# RAWX_Logger_Switches.net
KiCad netlist of a schematic drawn in EAGLE
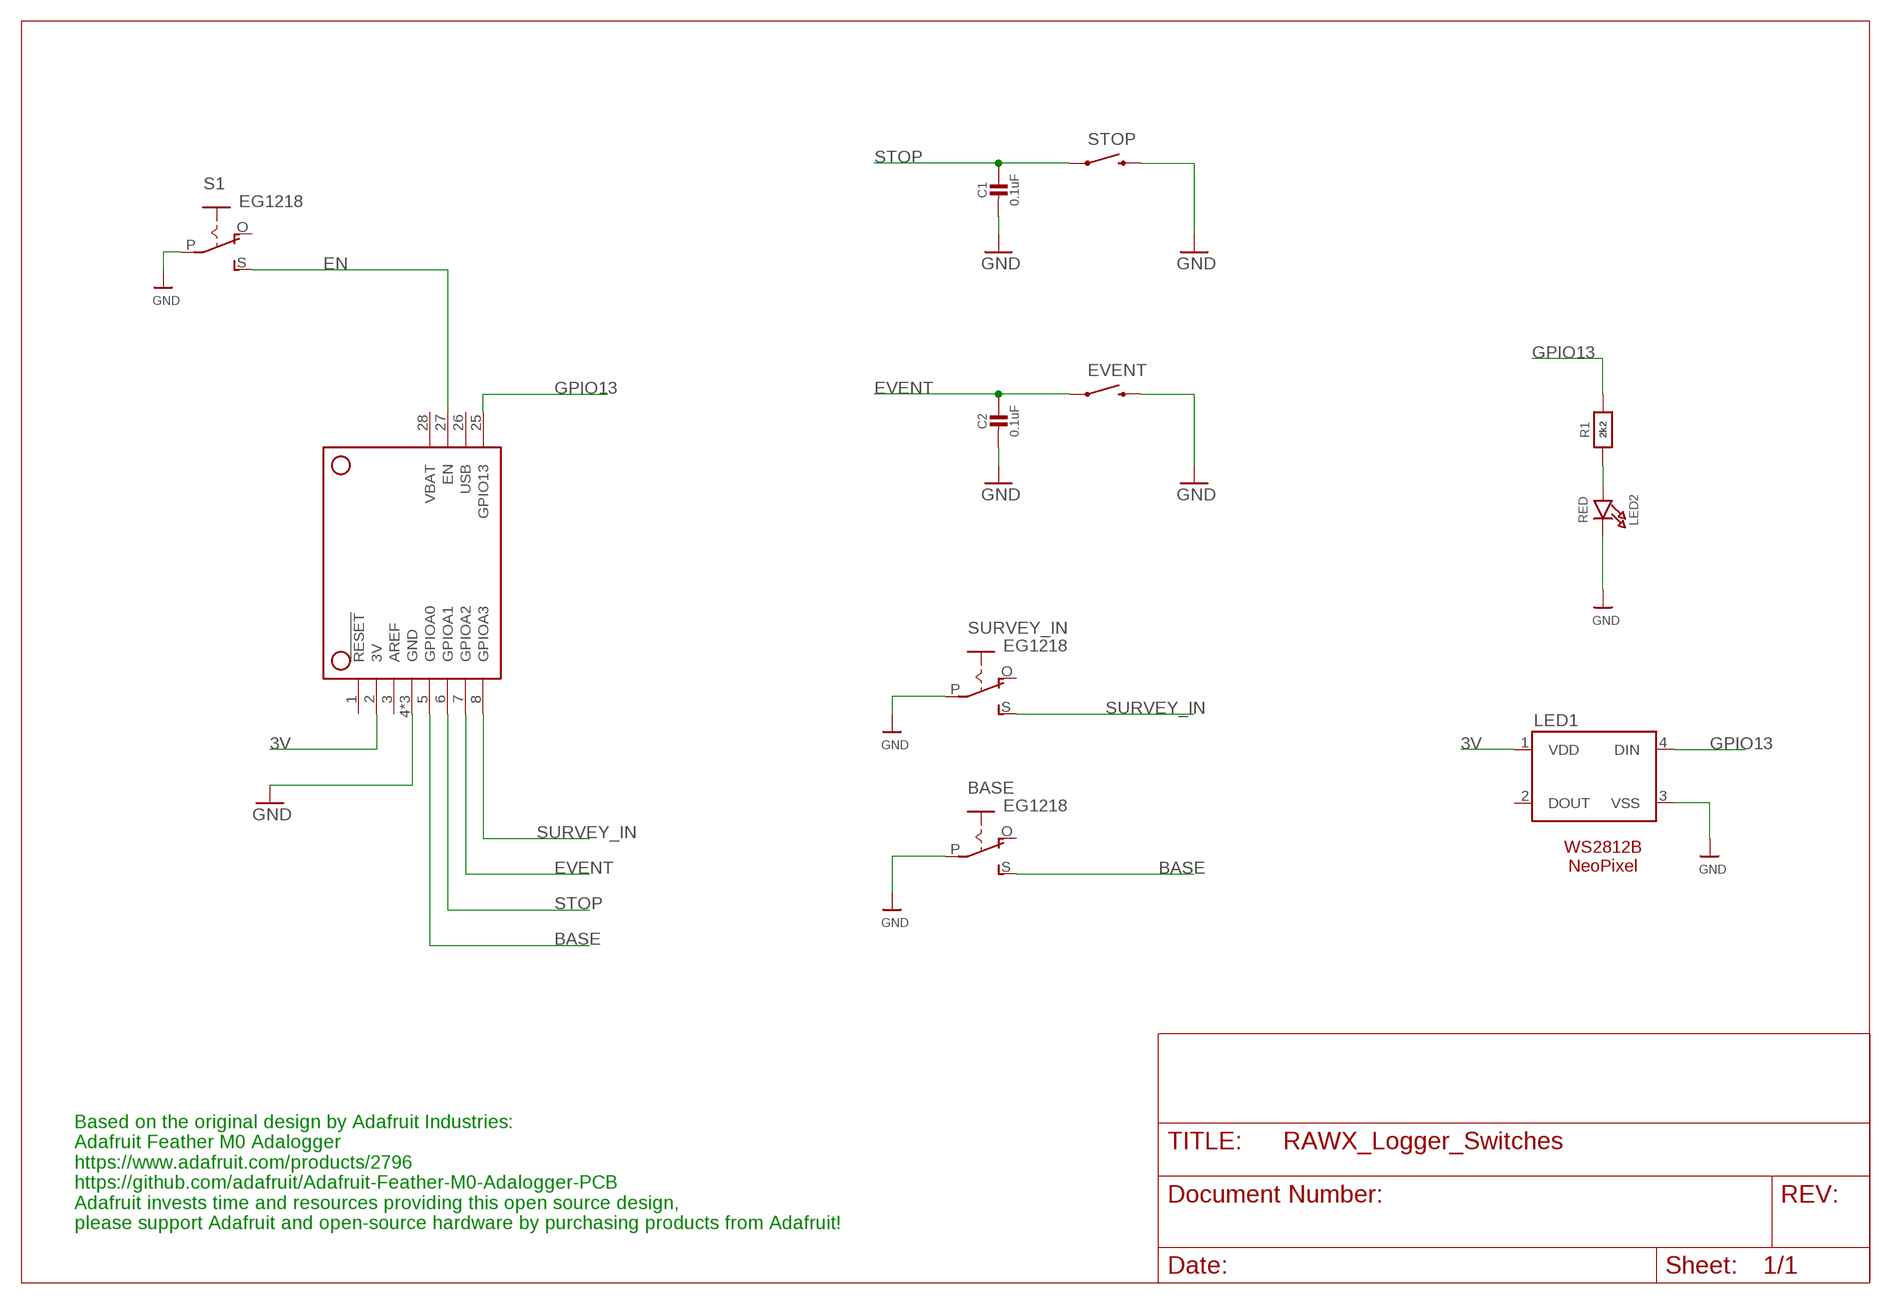
[diagram p0: schematic, sheet 1]

(export (version "E")
  (design (tool "Eeschema 10.0.6"))
  (components
    (comp (ref "BASE")
      (value "EG1218")
      (footprint "eagle-import:EG1218")
      (libsource (lib "eagle-import") (part "EG1218S"))
    )
    (comp (ref "C1")
      (value "0.1uF")
      (footprint "eagle-import:0603-NO")
      (libsource (lib "eagle-import") (part "CAP_CERAMIC0603_NO"))
    )
    (comp (ref "C2")
      (value "0.1uF")
      (footprint "eagle-import:0603-NO")
      (libsource (lib "eagle-import") (part "CAP_CERAMIC0603_NO"))
    )
    (comp (ref "EVENT")
      (value "SWITCH-MOMENTARY-2PTH")
      (footprint "eagle-import:TACTILE-PTH")
      (libsource (lib "eagle-import") (part "SWITCH-MOMENTARY-2PTH"))
    )
    (comp (ref "LED1")
      (value "WS2812B")
      (footprint "eagle-import:WS2812B")
      (libsource (lib "eagle-import") (part "WS2812B"))
    )
    (comp (ref "LED2")
      (value "RED")
      (footprint "eagle-import:CHIPLED_0805_NOOUTLINE")
      (libsource (lib "eagle-import") (part "LED0805_NOOUTLINE"))
    )
    (comp (ref "MS1")
      (value "MICROBUILDER_FEATHERWING_EN_SWITCH")
      (footprint "eagle-import:MICROBUILDER_FEATHERWING_EN_SWITCH")
      (libsource (lib "eagle-import") (part "MICROBUILDER_FEATHERWING_EN_SWITCH"))
    )
    (comp (ref "R1")
      (value "2k2")
      (footprint "eagle-import:0805-NO")
      (libsource (lib "eagle-import") (part "RESISTOR0805_NOOUTLINE"))
    )
    (comp (ref "S1")
      (value "EG1218")
      (footprint "eagle-import:EG1218")
      (libsource (lib "eagle-import") (part "EG1218S"))
    )
    (comp (ref "STOP")
      (value "SWITCH-MOMENTARY-2PTH")
      (footprint "eagle-import:TACTILE-PTH")
      (libsource (lib "eagle-import") (part "SWITCH-MOMENTARY-2PTH"))
    )
    (comp (ref "SURVEY_IN")
      (value "EG1218")
      (footprint "eagle-import:EG1218")
      (libsource (lib "eagle-import") (part "EG1218S"))
    )
  )
  (nets
    (net (code "1") (name "/3V") (class "Default")
      (node (ref "LED1") (pin "1") (pinfunction "VDD_1") (pintype "power_in"))
      (node (ref "MS1") (pin "2") (pinfunction "3V_2") (pintype "power_in"))
    )
    (net (code "2") (name "/BASE") (class "Default")
      (node (ref "BASE") (pin "S") (pinfunction "S_S") (pintype "passive"))
      (node (ref "MS1") (pin "5") (pinfunction "GPIOA0_5") (pintype "bidirectional"))
    )
    (net (code "3") (name "/EN") (class "Default")
      (node (ref "MS1") (pin "27") (pinfunction "EN_27") (pintype "passive"))
      (node (ref "S1") (pin "S") (pinfunction "S_S") (pintype "passive"))
    )
    (net (code "4") (name "/EVENT") (class "Default")
      (node (ref "C2") (pin "1") (pinfunction "1_1") (pintype "passive"))
      (node (ref "EVENT") (pin "1") (pinfunction "1_1") (pintype "passive"))
      (node (ref "MS1") (pin "7") (pinfunction "GPIOA2_7") (pintype "bidirectional"))
    )
    (net (code "5") (name "/GPIO13") (class "Default")
      (node (ref "LED1") (pin "4") (pinfunction "DIN_4") (pintype "input"))
      (node (ref "MS1") (pin "25") (pinfunction "GPIO13_25") (pintype "bidirectional"))
      (node (ref "R1") (pin "2") (pinfunction "2_2") (pintype "passive"))
    )
    (net (code "6") (name "/STOP") (class "Default")
      (node (ref "C1") (pin "1") (pinfunction "1_1") (pintype "passive"))
      (node (ref "MS1") (pin "6") (pinfunction "GPIOA1_6") (pintype "bidirectional"))
      (node (ref "STOP") (pin "1") (pinfunction "1_1") (pintype "passive"))
    )
    (net (code "7") (name "/SURVEY_IN") (class "Default")
      (node (ref "MS1") (pin "8") (pinfunction "GPIOA3_8") (pintype "bidirectional"))
      (node (ref "SURVEY_IN") (pin "S") (pinfunction "S_S") (pintype "passive"))
    )
    (net (code "8") (name "/USB") (class "Default")
      (node (ref "MS1") (pin "26") (pinfunction "USB_26") (pintype "power_in"))
    )
    (net (code "9") (name "/VBAT") (class "Default")
      (node (ref "MS1") (pin "28") (pinfunction "VBAT_28") (pintype "power_in"))
    )
    (net (code "10") (name "GND") (class "Default")
      (node (ref "BASE") (pin "P") (pinfunction "P_P") (pintype "passive"))
      (node (ref "C1") (pin "2") (pinfunction "2_2") (pintype "passive"))
      (node (ref "C2") (pin "2") (pinfunction "2_2") (pintype "passive"))
      (node (ref "EVENT") (pin "3") (pinfunction "2_3") (pintype "passive"))
      (node (ref "LED1") (pin "3") (pinfunction "VSS_3") (pintype "power_in"))
      (node (ref "LED2") (pin "C") (pinfunction "C_C") (pintype "passive"))
      (node (ref "MS1") (pin "4") (pinfunction "GND_4") (pintype "power_in"))
      (node (ref "MS1") (pin "P$1") (pinfunction "GND_P$1") (pintype "power_in"))
      (node (ref "MS1") (pin "P$2") (pinfunction "GND_P$2") (pintype "power_in"))
      (node (ref "S1") (pin "P") (pinfunction "P_P") (pintype "passive"))
      (node (ref "STOP") (pin "3") (pinfunction "2_3") (pintype "passive"))
      (node (ref "SURVEY_IN") (pin "P") (pinfunction "P_P") (pintype "passive"))
    )
    (net (code "11") (name "Net-(LED2-PadA)") (class "Default")
      (node (ref "LED2") (pin "A") (pinfunction "A_A") (pintype "passive"))
      (node (ref "R1") (pin "1") (pinfunction "1_1") (pintype "passive"))
    )
    (net (code "12") (name "unconnected-(BASE-PadO)") (class "Default")
      (node (ref "BASE") (pin "O") (pinfunction "O_O") (pintype "passive"))
    )
    (net (code "13") (name "unconnected-(LED1-DOUT-Pad2)") (class "Default")
      (node (ref "LED1") (pin "2") (pinfunction "DOUT_2") (pintype "output"))
    )
    (net (code "14") (name "unconnected-(MS1-AREF-Pad3)") (class "Default")
      (node (ref "MS1") (pin "3") (pinfunction "AREF_3") (pintype "passive"))
    )
    (net (code "15") (name "unconnected-(MS1-~{RESET}-Pad1)") (class "Default")
      (node (ref "MS1") (pin "1") (pinfunction "~{RESET}_1") (pintype "input"))
    )
    (net (code "16") (name "unconnected-(S1-PadO)") (class "Default")
      (node (ref "S1") (pin "O") (pinfunction "O_O") (pintype "passive"))
    )
    (net (code "17") (name "unconnected-(SURVEY_IN-PadO)") (class "Default")
      (node (ref "SURVEY_IN") (pin "O") (pinfunction "O_O") (pintype "passive"))
    )
  )
)
